# London_EPS-v_2_0.net
KiCad netlist of a schematic drawn in EAGLE
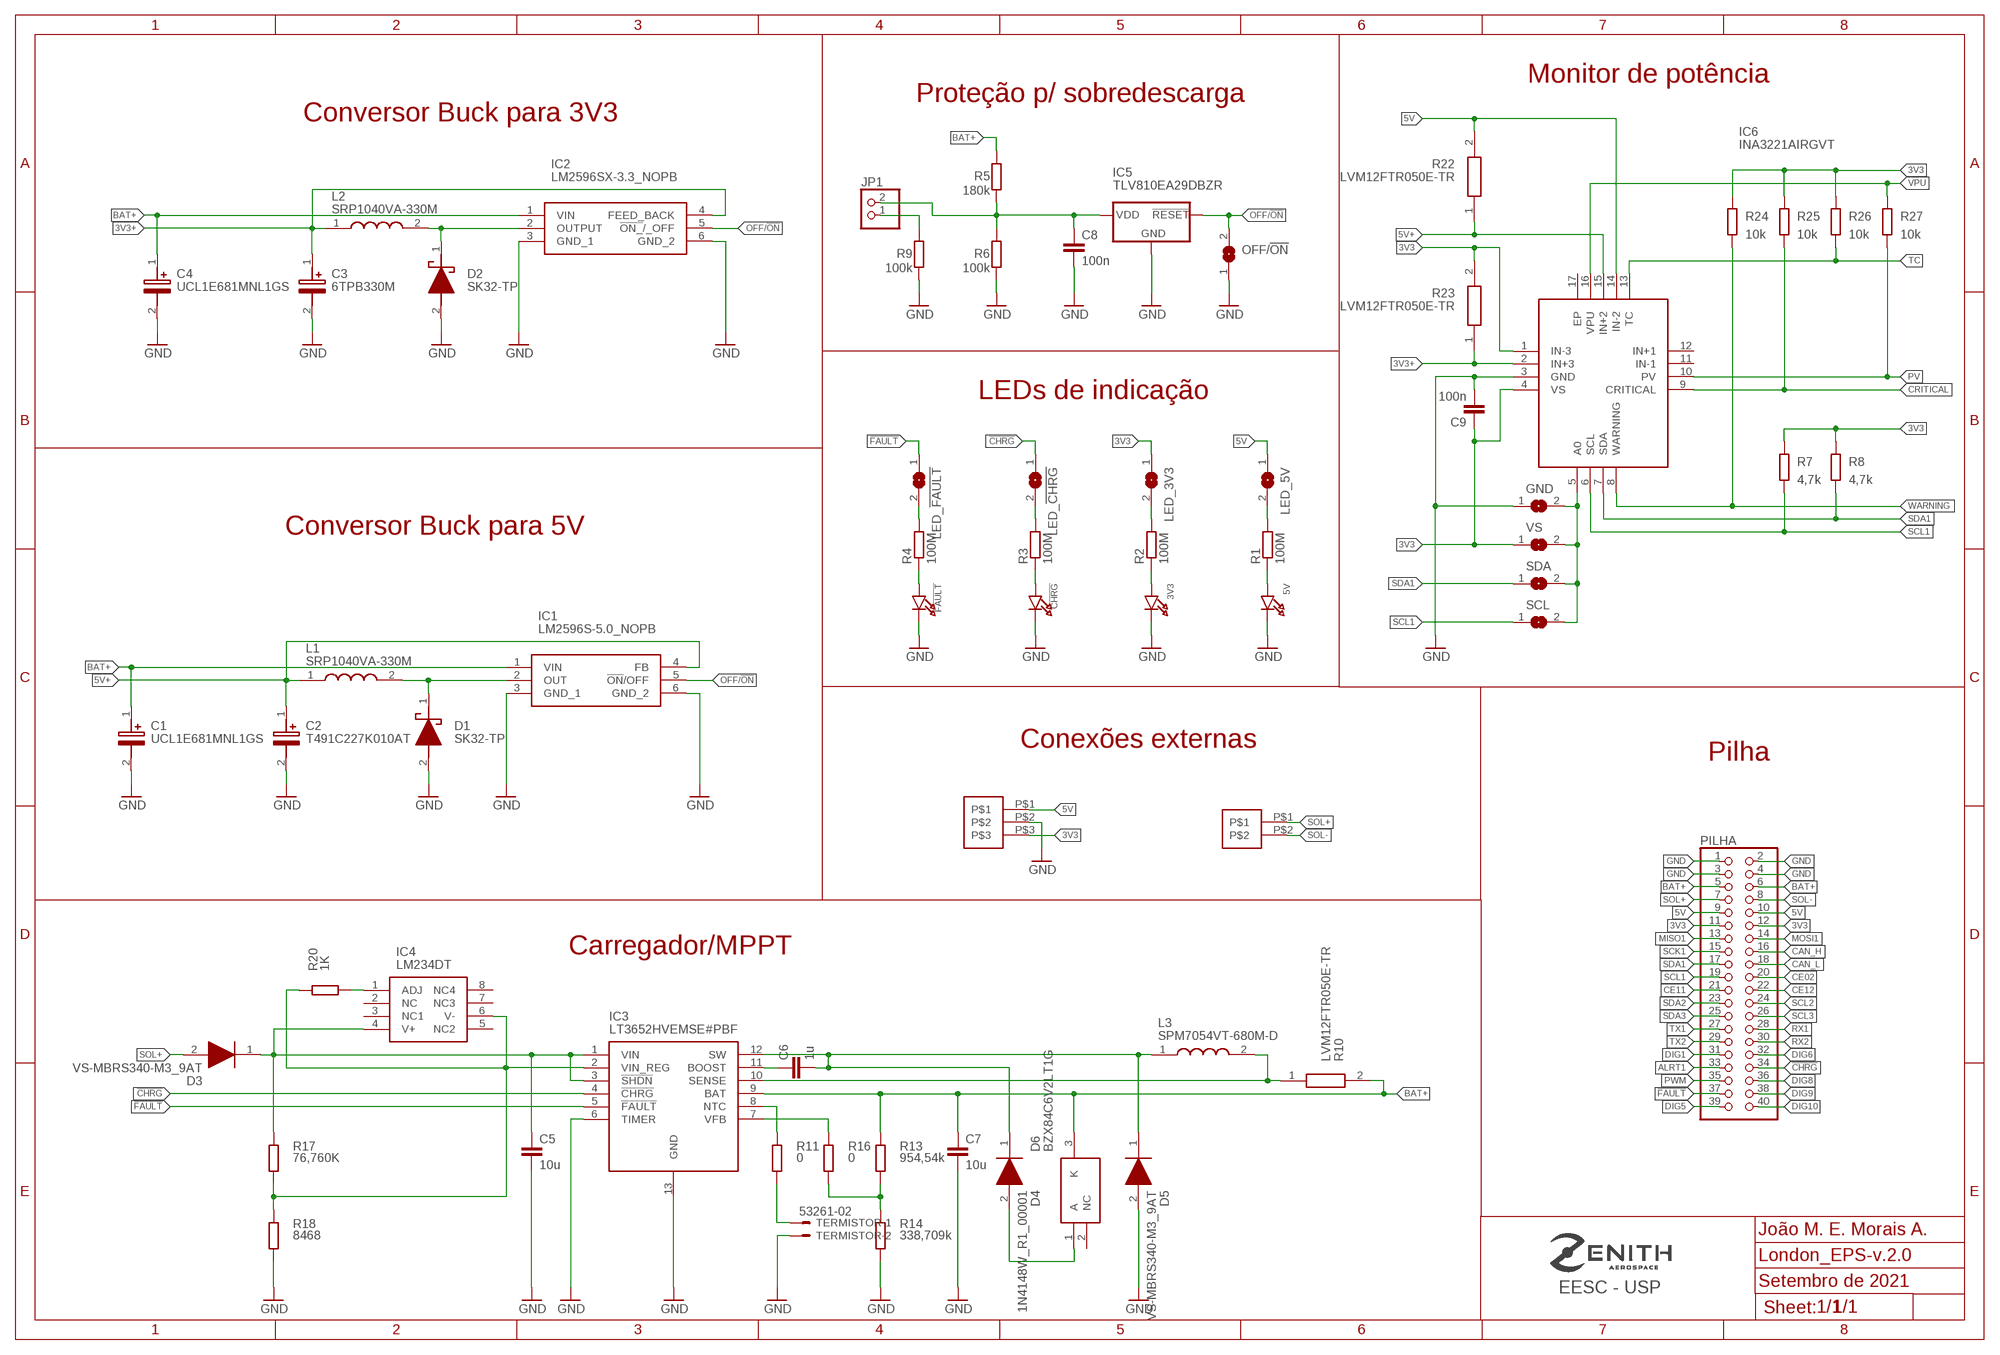
[diagram p0: schematic, sheet 1]

(export (version "E")
  (design (tool "Eeschema 10.0.6"))
  (components
    (comp (ref "!CHRG")
      (value "LED1206")
      (footprint "eagle-import:CHIPLED_1206")
      (libsource (lib "eagle-import") (part "LED1206"))
    )
    (comp (ref "!FAULT")
      (value "LED1206")
      (footprint "eagle-import:CHIPLED_1206")
      (libsource (lib "eagle-import") (part "LED1206"))
    )
    (comp (ref "3V3")
      (value "LED1206")
      (footprint "eagle-import:CHIPLED_1206")
      (libsource (lib "eagle-import") (part "LED1206"))
    )
    (comp (ref "5V")
      (value "LED1206")
      (footprint "eagle-import:CHIPLED_1206")
      (libsource (lib "eagle-import") (part "LED1206"))
    )
    (comp (ref "C1")
      (value "UCL1E681MNL1GS")
      (footprint "eagle-import:CAPAE1030X1400N")
      (fields (field (name "MOUSER_PART_NUMBER") "647-UCL1E681MNL1GS"))
      (libsource (lib "eagle-import") (part "UCL1E681MNL1GS"))
    )
    (comp (ref "C2")
      (value "T491C227K010AT")
      (footprint "eagle-import:CAPPM6032X280N")
      (fields (field (name "MOUSER_PART_NUMBER") "80-T491C227K010AT"))
      (libsource (lib "eagle-import") (part "T491C227K010AT"))
    )
    (comp (ref "C3")
      (value "6TPB330M")
      (footprint "eagle-import:10TPF150ML")
      (fields (field (name "MOUSER_PART_NUMBER") "667-6TPB330M"))
      (libsource (lib "eagle-import") (part "6TPB330M"))
    )
    (comp (ref "C4")
      (value "UCL1E681MNL1GS")
      (footprint "eagle-import:CAPAE1030X1400N")
      (fields (field (name "MOUSER_PART_NUMBER") "647-UCL1E681MNL1GS"))
      (libsource (lib "eagle-import") (part "UCL1E681MNL1GS"))
    )
    (comp (ref "C5")
      (value "10u")
      (footprint "eagle-import:C0805")
      (libsource (lib "eagle-import") (part "C-EUC0805"))
    )
    (comp (ref "C6")
      (value "1u")
      (footprint "eagle-import:C0805")
      (libsource (lib "eagle-import") (part "C-EUC0805"))
    )
    (comp (ref "C7")
      (value "10u")
      (footprint "eagle-import:C0805")
      (libsource (lib "eagle-import") (part "C-EUC0805"))
    )
    (comp (ref "C8")
      (value "100n")
      (footprint "eagle-import:C0805")
      (libsource (lib "eagle-import") (part "C-EUC0805"))
    )
    (comp (ref "C9")
      (value "100n")
      (footprint "eagle-import:C0805")
      (libsource (lib "eagle-import") (part "C-EUC0805"))
    )
    (comp (ref "D1")
      (value "SK32-TP")
      (footprint "eagle-import:DIOM7959X262N@1")
      (fields (field (name "MOUSER_PART_NUMBER") "833-SK32-TP"))
      (libsource (lib "eagle-import") (part "SK32-TP"))
    )
    (comp (ref "D2")
      (value "SK32-TP")
      (footprint "eagle-import:DIOM7959X262N@1")
      (fields (field (name "MOUSER_PART_NUMBER") "833-SK32-TP"))
      (libsource (lib "eagle-import") (part "SK32-TP"))
    )
    (comp (ref "D3")
      (value "VS-MBRS340-M3_9AT")
      (footprint "eagle-import:DIOM7959X262N")
      (fields
        (field (name "MANUFACTURER_PART_NUMBER") "VS-MBRS340-M3/9AT")
        (field (name "MOUSER_PART_NUMBER") "78-VS-MBRS340-M39AT")
      )
      (libsource (lib "eagle-import") (part "VS-MBRS340-M3_9AT"))
    )
    (comp (ref "D4")
      (value "1N4148W_R1_00001")
      (footprint "eagle-import:SOD3816X135N")
      (fields (field (name "MOUSER_PART_NUMBER") "241-1N4148W_R1_00001"))
      (libsource (lib "eagle-import") (part "1N4148W_R1_00001"))
    )
    (comp (ref "D5")
      (value "VS-MBRS340-M3_9AT")
      (footprint "eagle-import:DIOM7959X262N")
      (fields
        (field (name "MANUFACTURER_PART_NUMBER") "VS-MBRS340-M3/9AT")
        (field (name "MOUSER_PART_NUMBER") "78-VS-MBRS340-M39AT")
      )
      (libsource (lib "eagle-import") (part "VS-MBRS340-M3_9AT"))
    )
    (comp (ref "D6")
      (value "BZX84C6V2LT1G")
      (footprint "eagle-import:SOT96P237X111-3N")
      (fields (field (name "MOUSER_PART_NUMBER") "863-BZX84C6V2LT1G"))
      (libsource (lib "eagle-import") (part "BZX84C6V2LT1G"))
    )
    (comp (ref "GND")
      (value "SOLDERJUMPERREFLOW_NOPASTE")
      (footprint "eagle-import:SOLDERJUMPER_REFLOW_NOPASTE")
      (libsource (lib "eagle-import") (part "SOLDERJUMPERREFLOW_NOPASTE"))
    )
    (comp (ref "IC1")
      (value "LM2596S-5.0_NOPB")
      (footprint "eagle-import:KTT0005B")
      (fields
        (field (name "MANUFACTURER_PART_NUMBER") "LM2596S-5.0/NOPB")
        (field (name "MOUSER_PART_NUMBER") "926-LM2596S-5.0/NOPB")
      )
      (libsource (lib "eagle-import") (part "LM2596S-5.0_NOPB"))
    )
    (comp (ref "IC2")
      (value "LM2596SX-3.3_NOPB")
      (footprint "eagle-import:KTT0005B")
      (fields
        (field (name "MANUFACTURER_PART_NUMBER") "LM2596SX-3.3/NOPB")
        (field (name "MOUSER_PART_NUMBER") "926-LM2596SX33NOPB")
      )
      (libsource (lib "eagle-import") (part "LM2596SX-3.3_NOPB"))
    )
    (comp (ref "IC3")
      (value "LT3652HVEMSE#PBF")
      (footprint "eagle-import:SOP65P490X110-13N")
      (fields (field (name "MOUSER_PART_NUMBER") "584-LT3652HVEMSE#PBF"))
      (libsource (lib "eagle-import") (part "LT3652HVEMSE#PBF"))
    )
    (comp (ref "IC4")
      (value "LM234DT")
      (footprint "eagle-import:SOIC127P600X175-8N")
      (fields (field (name "MOUSER_PART_NUMBER") "511-LM234D"))
      (libsource (lib "eagle-import") (part "LM234DT"))
    )
    (comp (ref "IC5")
      (value "TLV810EA29DBZR")
      (footprint "eagle-import:SOT23")
      (libsource (lib "eagle-import") (part "TLV810EA29DBZR"))
    )
    (comp (ref "IC6")
      (value "INA3221AIRGVT")
      (footprint "eagle-import:QFN65P400X400X100-17N")
      (fields (field (name "MOUSER_PART_NUMBER") "595-INA3221AIRGVT"))
      (libsource (lib "eagle-import") (part "INA3221AIRGVT"))
    )
    (comp (ref "JP1")
      (value "PINHD-1X2/90")
      (footprint "eagle-import:1X02_90")
      (libsource (lib "eagle-import") (part "PINHD-1X2/90"))
    )
    (comp (ref "L1")
      (value "SRP1040VA-330M")
      (footprint "eagle-import:INDPM110100X400N")
      (fields (field (name "MOUSER_PART_NUMBER") "652-SRP1040VA-330M"))
      (libsource (lib "eagle-import") (part "SRP1040VA-330M"))
    )
    (comp (ref "L2")
      (value "SRP1040VA-330M")
      (footprint "eagle-import:INDPM110100X400N")
      (fields (field (name "MOUSER_PART_NUMBER") "652-SRP1040VA-330M"))
      (libsource (lib "eagle-import") (part "SRP1040VA-330M"))
    )
    (comp (ref "L3")
      (value "SPM7054VT-680M-D")
      (footprint "eagle-import:SPM7054VT")
      (fields (field (name "MOUSER_PART_NUMBER") "810-SPM7054VT-680M-D"))
      (libsource (lib "eagle-import") (part "SPM7054VT-680M-D"))
    )
    (comp (ref "LED_!CHRG")
      (value "SOLDERJUMPERREFLOW_NOPASTE")
      (footprint "eagle-import:SOLDERJUMPER_REFLOW_NOPASTE")
      (libsource (lib "eagle-import") (part "SOLDERJUMPERREFLOW_NOPASTE"))
    )
    (comp (ref "LED_!FAULT")
      (value "SOLDERJUMPERREFLOW_NOPASTE")
      (footprint "eagle-import:SOLDERJUMPER_REFLOW_NOPASTE")
      (libsource (lib "eagle-import") (part "SOLDERJUMPERREFLOW_NOPASTE"))
    )
    (comp (ref "LED_3V3")
      (value "SOLDERJUMPERREFLOW_NOPASTE")
      (footprint "eagle-import:SOLDERJUMPER_REFLOW_NOPASTE")
      (libsource (lib "eagle-import") (part "SOLDERJUMPERREFLOW_NOPASTE"))
    )
    (comp (ref "LED_5V")
      (value "SOLDERJUMPERREFLOW_NOPASTE")
      (footprint "eagle-import:SOLDERJUMPER_REFLOW_NOPASTE")
      (libsource (lib "eagle-import") (part "SOLDERJUMPERREFLOW_NOPASTE"))
    )
    (comp (ref "OFF/!ON")
      (value "SOLDERJUMPERREFLOW_NOPASTE")
      (footprint "eagle-import:SOLDERJUMPER_REFLOW_NOPASTE")
      (libsource (lib "eagle-import") (part "SOLDERJUMPERREFLOW_NOPASTE"))
    )
    (comp (ref "PILHA")
      (value "PINHD-2X20")
      (footprint "eagle-import:2X20")
      (libsource (lib "eagle-import") (part "PINHD-2X20"))
    )
    (comp (ref "R1")
      (value "100M")
      (footprint "eagle-import:R0805")
      (libsource (lib "eagle-import") (part "R-EU_R0805"))
    )
    (comp (ref "R2")
      (value "100M")
      (footprint "eagle-import:R0805")
      (libsource (lib "eagle-import") (part "R-EU_R0805"))
    )
    (comp (ref "R3")
      (value "100M")
      (footprint "eagle-import:R0805")
      (libsource (lib "eagle-import") (part "R-EU_R0805"))
    )
    (comp (ref "R4")
      (value "100M")
      (footprint "eagle-import:R0805")
      (libsource (lib "eagle-import") (part "R-EU_R0805"))
    )
    (comp (ref "R5")
      (value "180k")
      (footprint "eagle-import:R0805")
      (libsource (lib "eagle-import") (part "R-EU_R0805"))
    )
    (comp (ref "R6")
      (value "100k")
      (footprint "eagle-import:R0805")
      (libsource (lib "eagle-import") (part "R-EU_R0805"))
    )
    (comp (ref "R7")
      (value "4,7k")
      (footprint "eagle-import:R0805")
      (libsource (lib "eagle-import") (part "R-EU_R0805"))
    )
    (comp (ref "R8")
      (value "4,7k")
      (footprint "eagle-import:R0805")
      (libsource (lib "eagle-import") (part "R-EU_R0805"))
    )
    (comp (ref "R9")
      (value "100k")
      (footprint "eagle-import:R0805")
      (libsource (lib "eagle-import") (part "R-EU_R0805"))
    )
    (comp (ref "R10")
      (value "LVM12FTR050E-TR")
      (footprint "eagle-import:RESC3016X70N")
      (fields (field (name "MOUSER_PART_NUMBER") "588-LVM12FTR050E-TR"))
      (libsource (lib "eagle-import") (part "LVM12FTR050E-TR"))
    )
    (comp (ref "R11")
      (value "0")
      (footprint "eagle-import:R0805")
      (libsource (lib "eagle-import") (part "R-EU_R0805"))
    )
    (comp (ref "R13")
      (value "954,54k")
      (footprint "eagle-import:R0805")
      (libsource (lib "eagle-import") (part "R-EU_R0805"))
    )
    (comp (ref "R14")
      (value "338,709k")
      (footprint "eagle-import:R0805")
      (libsource (lib "eagle-import") (part "R-EU_R0805"))
    )
    (comp (ref "R16")
      (value "0")
      (footprint "eagle-import:R0805")
      (libsource (lib "eagle-import") (part "R-EU_R0805"))
    )
    (comp (ref "R17")
      (value "76,760K")
      (footprint "eagle-import:R0805")
      (libsource (lib "eagle-import") (part "R-EU_R0805"))
    )
    (comp (ref "R18")
      (value "8468")
      (footprint "eagle-import:R0805")
      (libsource (lib "eagle-import") (part "R-EU_R0805"))
    )
    (comp (ref "R20")
      (value "1K")
      (footprint "eagle-import:R0805")
      (libsource (lib "eagle-import") (part "R-EU_R0805"))
    )
    (comp (ref "R22")
      (value "LVM12FTR050E-TR")
      (footprint "eagle-import:RESC3016X70N")
      (fields (field (name "MOUSER_PART_NUMBER") "588-LVM12FTR050E-TR"))
      (libsource (lib "eagle-import") (part "LVM12FTR050E-TR"))
    )
    (comp (ref "R23")
      (value "LVM12FTR050E-TR")
      (footprint "eagle-import:RESC3016X70N")
      (fields (field (name "MOUSER_PART_NUMBER") "588-LVM12FTR050E-TR"))
      (libsource (lib "eagle-import") (part "LVM12FTR050E-TR"))
    )
    (comp (ref "R24")
      (value "10k")
      (footprint "eagle-import:R0805")
      (libsource (lib "eagle-import") (part "R-EU_R0805"))
    )
    (comp (ref "R25")
      (value "10k")
      (footprint "eagle-import:R0805")
      (libsource (lib "eagle-import") (part "R-EU_R0805"))
    )
    (comp (ref "R26")
      (value "10k")
      (footprint "eagle-import:R0805")
      (libsource (lib "eagle-import") (part "R-EU_R0805"))
    )
    (comp (ref "R27")
      (value "10k")
      (footprint "eagle-import:R0805")
      (libsource (lib "eagle-import") (part "R-EU_R0805"))
    )
    (comp (ref "SCL")
      (value "SOLDERJUMPERREFLOW_NOPASTE")
      (footprint "eagle-import:SOLDERJUMPER_REFLOW_NOPASTE")
      (libsource (lib "eagle-import") (part "SOLDERJUMPERREFLOW_NOPASTE"))
    )
    (comp (ref "SDA")
      (value "SOLDERJUMPERREFLOW_NOPASTE")
      (footprint "eagle-import:SOLDERJUMPER_REFLOW_NOPASTE")
      (libsource (lib "eagle-import") (part "SOLDERJUMPERREFLOW_NOPASTE"))
    )
    (comp (ref "TERMISTOR")
      (value "53261-02")
      (footprint "eagle-import:53261-02")
      (fields (field (name "MF") "MOLEX"))
      (libsource (lib "eagle-import") (part "53?-02261"))
    )
    (comp (ref "U$1")
      (value "S02B-XASS-1")
      (footprint "eagle-import:S02B-XASS-1")
      (libsource (lib "eagle-import") (part "S02B-XASS-1"))
    )
    (comp (ref "U$2")
      (value "S03B-XASS-1")
      (footprint "eagle-import:S03B-XASS-1")
      (libsource (lib "eagle-import") (part "S03B-XASS-1"))
    )
    (comp (ref "VS")
      (value "SOLDERJUMPERREFLOW_NOPASTE")
      (footprint "eagle-import:SOLDERJUMPER_REFLOW_NOPASTE")
      (libsource (lib "eagle-import") (part "SOLDERJUMPERREFLOW_NOPASTE"))
    )
  )
  (nets
    (net (code "1") (name "/OFF{slash}~{ON}") (class "Default")
      (node (ref "IC1") (pin "5") (pinfunction "~{ON}/OFF_5") (pintype "bidirectional"))
      (node (ref "IC2") (pin "5") (pinfunction "~{ON_}/_OFF_5") (pintype "bidirectional"))
      (node (ref "IC5") (pin "1") (pinfunction "~{RESET}_1") (pintype "passive"))
      (node (ref "OFF/!ON") (pin "2") (pinfunction "2_2") (pintype "passive"))
    )
    (net (code "2") (name "/~{CHRG}") (class "Default")
      (node (ref "IC3") (pin "4") (pinfunction "~{CHRG}_4") (pintype "bidirectional"))
      (node (ref "LED_!CHRG") (pin "1") (pinfunction "1_1") (pintype "passive"))
      (node (ref "PILHA") (pin "34") (pinfunction "34_34") (pintype "passive"))
    )
    (net (code "3") (name "/~{FAULT}") (class "Default")
      (node (ref "IC3") (pin "5") (pinfunction "~{FAULT}_5") (pintype "bidirectional"))
      (node (ref "LED_!FAULT") (pin "1") (pinfunction "1_1") (pintype "passive"))
      (node (ref "PILHA") (pin "37") (pinfunction "37_37") (pintype "passive"))
    )
    (net (code "4") (name "3V3") (class "Default")
      (node (ref "C9") (pin "1") (pinfunction "1_1") (pintype "passive"))
      (node (ref "IC6") (pin "1") (pinfunction "IN-3_1") (pintype "bidirectional"))
      (node (ref "IC6") (pin "4") (pinfunction "VS_4") (pintype "bidirectional"))
      (node (ref "LED_3V3") (pin "1") (pinfunction "1_1") (pintype "passive"))
      (node (ref "PILHA") (pin "11") (pinfunction "11_11") (pintype "passive"))
      (node (ref "PILHA") (pin "12") (pinfunction "12_12") (pintype "passive"))
      (node (ref "R23") (pin "2") (pinfunction "2_2") (pintype "bidirectional"))
      (node (ref "R24") (pin "2") (pinfunction "2_2") (pintype "passive"))
      (node (ref "R25") (pin "2") (pinfunction "2_2") (pintype "passive"))
      (node (ref "R26") (pin "2") (pinfunction "2_2") (pintype "passive"))
      (node (ref "R7") (pin "2") (pinfunction "2_2") (pintype "passive"))
      (node (ref "R8") (pin "2") (pinfunction "2_2") (pintype "passive"))
      (node (ref "U$2") (pin "P$3") (pinfunction "P$3_P$3") (pintype "bidirectional"))
      (node (ref "VS") (pin "1") (pinfunction "1_1") (pintype "passive"))
    )
    (net (code "5") (name "3V3+") (class "Default")
      (node (ref "C3") (pin "1") (pinfunction "+_1") (pintype "bidirectional"))
      (node (ref "IC2") (pin "4") (pinfunction "FEED_BACK_4") (pintype "bidirectional"))
      (node (ref "IC6") (pin "2") (pinfunction "IN+3_2") (pintype "bidirectional"))
      (node (ref "L2") (pin "1") (pinfunction "1_1") (pintype "bidirectional"))
      (node (ref "R23") (pin "1") (pinfunction "1_1") (pintype "bidirectional"))
    )
    (net (code "6") (name "5V") (class "Default")
      (node (ref "IC6") (pin "14") (pinfunction "IN-2_14") (pintype "bidirectional"))
      (node (ref "LED_5V") (pin "1") (pinfunction "1_1") (pintype "passive"))
      (node (ref "PILHA") (pin "10") (pinfunction "10_10") (pintype "passive"))
      (node (ref "PILHA") (pin "9") (pinfunction "9_9") (pintype "passive"))
      (node (ref "R22") (pin "2") (pinfunction "2_2") (pintype "bidirectional"))
      (node (ref "U$2") (pin "P$1") (pinfunction "P$1_P$1") (pintype "bidirectional"))
    )
    (net (code "7") (name "5V+") (class "Default")
      (node (ref "C2") (pin "1") (pinfunction "+_1") (pintype "bidirectional"))
      (node (ref "IC1") (pin "4") (pinfunction "FB_4") (pintype "bidirectional"))
      (node (ref "IC6") (pin "15") (pinfunction "IN+2_15") (pintype "bidirectional"))
      (node (ref "L1") (pin "1") (pinfunction "1_1") (pintype "bidirectional"))
      (node (ref "R22") (pin "1") (pinfunction "1_1") (pintype "bidirectional"))
    )
    (net (code "8") (name "ALRT1") (class "Default")
      (node (ref "PILHA") (pin "33") (pinfunction "33_33") (pintype "passive"))
    )
    (net (code "9") (name "BAT+") (class "Default")
      (node (ref "C1") (pin "1") (pinfunction "+_1") (pintype "bidirectional"))
      (node (ref "C4") (pin "1") (pinfunction "+_1") (pintype "bidirectional"))
      (node (ref "C7") (pin "1") (pinfunction "1_1") (pintype "passive"))
      (node (ref "D6") (pin "3") (pinfunction "K_3") (pintype "bidirectional"))
      (node (ref "IC1") (pin "1") (pinfunction "VIN_1") (pintype "bidirectional"))
      (node (ref "IC2") (pin "1") (pinfunction "VIN_1") (pintype "bidirectional"))
      (node (ref "IC3") (pin "9") (pinfunction "BAT_9") (pintype "bidirectional"))
      (node (ref "PILHA") (pin "5") (pinfunction "5_5") (pintype "passive"))
      (node (ref "PILHA") (pin "6") (pinfunction "6_6") (pintype "passive"))
      (node (ref "R10") (pin "2") (pinfunction "2_2") (pintype "bidirectional"))
      (node (ref "R13") (pin "1") (pinfunction "1_1") (pintype "passive"))
      (node (ref "R5") (pin "1") (pinfunction "1_1") (pintype "passive"))
    )
    (net (code "10") (name "CAN_H") (class "Default")
      (node (ref "PILHA") (pin "16") (pinfunction "16_16") (pintype "passive"))
    )
    (net (code "11") (name "CAN_L") (class "Default")
      (node (ref "PILHA") (pin "18") (pinfunction "18_18") (pintype "passive"))
    )
    (net (code "12") (name "CE02") (class "Default")
      (node (ref "PILHA") (pin "20") (pinfunction "20_20") (pintype "passive"))
    )
    (net (code "13") (name "CE11") (class "Default")
      (node (ref "PILHA") (pin "21") (pinfunction "21_21") (pintype "passive"))
    )
    (net (code "14") (name "CE12") (class "Default")
      (node (ref "PILHA") (pin "22") (pinfunction "22_22") (pintype "passive"))
    )
    (net (code "15") (name "CRITICAL") (class "Default")
      (node (ref "IC6") (pin "9") (pinfunction "CRITICAL_9") (pintype "bidirectional"))
      (node (ref "R25") (pin "1") (pinfunction "1_1") (pintype "passive"))
    )
    (net (code "16") (name "DIG1") (class "Default")
      (node (ref "PILHA") (pin "31") (pinfunction "31_31") (pintype "passive"))
    )
    (net (code "17") (name "DIG5") (class "Default")
      (node (ref "PILHA") (pin "39") (pinfunction "39_39") (pintype "passive"))
    )
    (net (code "18") (name "DIG6") (class "Default")
      (node (ref "PILHA") (pin "32") (pinfunction "32_32") (pintype "passive"))
    )
    (net (code "19") (name "DIG8") (class "Default")
      (node (ref "PILHA") (pin "36") (pinfunction "36_36") (pintype "passive"))
    )
    (net (code "20") (name "DIG9") (class "Default")
      (node (ref "PILHA") (pin "38") (pinfunction "38_38") (pintype "passive"))
    )
    (net (code "21") (name "DIG10") (class "Default")
      (node (ref "PILHA") (pin "40") (pinfunction "40_40") (pintype "passive"))
    )
    (net (code "22") (name "GND") (class "Default")
      (node (ref "!CHRG") (pin "C") (pinfunction "C_C") (pintype "passive"))
      (node (ref "!FAULT") (pin "C") (pinfunction "C_C") (pintype "passive"))
      (node (ref "3V3") (pin "C") (pinfunction "C_C") (pintype "passive"))
      (node (ref "5V") (pin "C") (pinfunction "C_C") (pintype "passive"))
      (node (ref "C1") (pin "2") (pinfunction "-_2") (pintype "bidirectional"))
      (node (ref "C2") (pin "2") (pinfunction "-_2") (pintype "bidirectional"))
      (node (ref "C3") (pin "2") (pinfunction "-_2") (pintype "bidirectional"))
      (node (ref "C4") (pin "2") (pinfunction "-_2") (pintype "bidirectional"))
      (node (ref "C5") (pin "2") (pinfunction "2_2") (pintype "passive"))
      (node (ref "C7") (pin "2") (pinfunction "2_2") (pintype "passive"))
      (node (ref "C8") (pin "2") (pinfunction "2_2") (pintype "passive"))
      (node (ref "C9") (pin "2") (pinfunction "2_2") (pintype "passive"))
      (node (ref "D1") (pin "2") (pinfunction "A_2") (pintype "bidirectional"))
      (node (ref "D2") (pin "2") (pinfunction "A_2") (pintype "bidirectional"))
      (node (ref "D5") (pin "2") (pinfunction "A_2") (pintype "bidirectional"))
      (node (ref "GND") (pin "1") (pinfunction "1_1") (pintype "passive"))
      (node (ref "IC1") (pin "3") (pinfunction "GND_1_3") (pintype "bidirectional"))
      (node (ref "IC1") (pin "6") (pinfunction "GND_2_6") (pintype "bidirectional"))
      (node (ref "IC2") (pin "3") (pinfunction "GND_1_3") (pintype "bidirectional"))
      (node (ref "IC2") (pin "6") (pinfunction "GND_2_6") (pintype "bidirectional"))
      (node (ref "IC3") (pin "13") (pinfunction "GND_13") (pintype "bidirectional"))
      (node (ref "IC3") (pin "6") (pinfunction "TIMER_6") (pintype "bidirectional"))
      (node (ref "IC5") (pin "2") (pinfunction "GND_2") (pintype "input"))
      (node (ref "IC6") (pin "3") (pinfunction "GND_3") (pintype "bidirectional"))
      (node (ref "OFF/!ON") (pin "1") (pinfunction "1_1") (pintype "passive"))
      (node (ref "PILHA") (pin "1") (pinfunction "1_1") (pintype "passive"))
      (node (ref "PILHA") (pin "2") (pinfunction "2_2") (pintype "passive"))
      (node (ref "PILHA") (pin "3") (pinfunction "3_3") (pintype "passive"))
      (node (ref "PILHA") (pin "4") (pinfunction "4_4") (pintype "passive"))
      (node (ref "R14") (pin "2") (pinfunction "2_2") (pintype "passive"))
      (node (ref "R18") (pin "2") (pinfunction "2_2") (pintype "passive"))
      (node (ref "R6") (pin "2") (pinfunction "2_2") (pintype "passive"))
      (node (ref "R9") (pin "2") (pinfunction "2_2") (pintype "passive"))
      (node (ref "TERMISTOR") (pin "2") (pinfunction "S_2") (pintype "passive"))
      (node (ref "U$2") (pin "P$2") (pinfunction "P$2_P$2") (pintype "bidirectional"))
    )
    (net (code "23") (name "MISO1") (class "Default")
      (node (ref "PILHA") (pin "13") (pinfunction "13_13") (pintype "passive"))
    )
    (net (code "24") (name "MOSI1") (class "Default")
      (node (ref "PILHA") (pin "14") (pinfunction "14_14") (pintype "passive"))
    )
    (net (code "25") (name "Net-(!CHRG-PadA)") (class "Default")
      (node (ref "!CHRG") (pin "A") (pinfunction "A_A") (pintype "passive"))
      (node (ref "R3") (pin "1") (pinfunction "1_1") (pintype "passive"))
    )
    (net (code "26") (name "Net-(!FAULT-PadA)") (class "Default")
      (node (ref "!FAULT") (pin "A") (pinfunction "A_A") (pintype "passive"))
      (node (ref "R4") (pin "1") (pinfunction "1_1") (pintype "passive"))
    )
    (net (code "27") (name "Net-(3V3-PadA)") (class "Default")
      (node (ref "3V3") (pin "A") (pinfunction "A_A") (pintype "passive"))
      (node (ref "R2") (pin "1") (pinfunction "1_1") (pintype "passive"))
    )
    (net (code "28") (name "Net-(5V-PadA)") (class "Default")
      (node (ref "5V") (pin "A") (pinfunction "A_A") (pintype "passive"))
      (node (ref "R1") (pin "1") (pinfunction "1_1") (pintype "passive"))
    )
    (net (code "29") (name "Net-(D1-K)") (class "Default")
      (node (ref "D1") (pin "1") (pinfunction "K_1") (pintype "bidirectional"))
      (node (ref "IC1") (pin "2") (pinfunction "OUT_2") (pintype "bidirectional"))
      (node (ref "L1") (pin "2") (pinfunction "2_2") (pintype "bidirectional"))
    )
    (net (code "30") (name "Net-(D2-K)") (class "Default")
      (node (ref "D2") (pin "1") (pinfunction "K_1") (pintype "bidirectional"))
      (node (ref "IC2") (pin "2") (pinfunction "OUTPUT_2") (pintype "bidirectional"))
      (node (ref "L2") (pin "2") (pinfunction "2_2") (pintype "bidirectional"))
    )
    (net (code "31") (name "Net-(D3-K)") (class "Default")
      (node (ref "C5") (pin "1") (pinfunction "1_1") (pintype "passive"))
      (node (ref "D3") (pin "1") (pinfunction "K_1") (pintype "bidirectional"))
      (node (ref "IC3") (pin "1") (pinfunction "VIN_1") (pintype "bidirectional"))
      (node (ref "IC3") (pin "3") (pinfunction "~{SHDN}_3") (pintype "bidirectional"))
      (node (ref "IC4") (pin "4") (pinfunction "V+_4") (pintype "bidirectional"))
      (node (ref "R17") (pin "1") (pinfunction "1_1") (pintype "passive"))
    )
    (net (code "32") (name "Net-(D4-A)") (class "Default")
      (node (ref "D4") (pin "2") (pinfunction "A_2") (pintype "bidirectional"))
      (node (ref "D6") (pin "1") (pinfunction "A_1") (pintype "bidirectional"))
    )
    (net (code "33") (name "Net-(D4-K)") (class "Default")
      (node (ref "C6") (pin "2") (pinfunction "2_2") (pintype "passive"))
      (node (ref "D4") (pin "1") (pinfunction "K_1") (pintype "bidirectional"))
      (node (ref "D5") (pin "1") (pinfunction "K_1") (pintype "bidirectional"))
      (node (ref "IC3") (pin "12") (pinfunction "SW_12") (pintype "bidirectional"))
      (node (ref "L3") (pin "1") (pinfunction "1_1") (pintype "bidirectional"))
    )
    (net (code "34") (name "Net-(IC3-BOOST)") (class "Default")
      (node (ref "C6") (pin "1") (pinfunction "1_1") (pintype "passive"))
      (node (ref "IC3") (pin "11") (pinfunction "BOOST_11") (pintype "bidirectional"))
    )
    (net (code "35") (name "Net-(IC3-NTC)") (class "Default")
      (node (ref "IC3") (pin "8") (pinfunction "NTC_8") (pintype "bidirectional"))
      (node (ref "R11") (pin "1") (pinfunction "1_1") (pintype "passive"))
    )
    (net (code "36") (name "Net-(IC3-SENSE)") (class "Default")
      (node (ref "IC3") (pin "10") (pinfunction "SENSE_10") (pintype "bidirectional"))
      (node (ref "L3") (pin "2") (pinfunction "2_2") (pintype "bidirectional"))
      (node (ref "R10") (pin "1") (pinfunction "1_1") (pintype "bidirectional"))
    )
    (net (code "37") (name "Net-(IC3-VFB)") (class "Default")
      (node (ref "IC3") (pin "7") (pinfunction "VFB_7") (pintype "bidirectional"))
      (node (ref "R16") (pin "1") (pinfunction "1_1") (pintype "passive"))
    )
    (net (code "38") (name "Net-(IC3-VIN_REG)") (class "Default")
      (node (ref "IC3") (pin "2") (pinfunction "VIN_REG_2") (pintype "bidirectional"))
      (node (ref "IC4") (pin "6") (pinfunction "V-_6") (pintype "bidirectional"))
      (node (ref "R17") (pin "2") (pinfunction "2_2") (pintype "passive"))
      (node (ref "R18") (pin "1") (pinfunction "1_1") (pintype "passive"))
      (node (ref "R20") (pin "1") (pinfunction "1_1") (pintype "passive"))
    )
    (net (code "39") (name "Net-(IC4-ADJ)") (class "Default")
      (node (ref "IC4") (pin "1") (pinfunction "ADJ_1") (pintype "bidirectional"))
      (node (ref "R20") (pin "2") (pinfunction "2_2") (pintype "passive"))
    )
    (net (code "40") (name "Net-(IC5-VDD)") (class "Default")
      (node (ref "C8") (pin "1") (pinfunction "1_1") (pintype "passive"))
      (node (ref "IC5") (pin "3") (pinfunction "VDD_3") (pintype "input"))
      (node (ref "JP1") (pin "2") (pinfunction "2_2") (pintype "passive"))
      (node (ref "R5") (pin "2") (pinfunction "2_2") (pintype "passive"))
      (node (ref "R6") (pin "1") (pinfunction "1_1") (pintype "passive"))
    )
    (net (code "41") (name "Net-(IC6-A0)") (class "Default")
      (node (ref "GND") (pin "2") (pinfunction "2_2") (pintype "passive"))
      (node (ref "IC6") (pin "5") (pinfunction "A0_5") (pintype "bidirectional"))
      (node (ref "SCL") (pin "2") (pinfunction "2_2") (pintype "passive"))
      (node (ref "SDA") (pin "2") (pinfunction "2_2") (pintype "passive"))
      (node (ref "VS") (pin "2") (pinfunction "2_2") (pintype "passive"))
    )
    (net (code "42") (name "Net-(JP1-Pad1)") (class "Default")
      (node (ref "JP1") (pin "1") (pinfunction "1_1") (pintype "passive"))
      (node (ref "R9") (pin "1") (pinfunction "1_1") (pintype "passive"))
    )
    (net (code "43") (name "Net-(LED_!CHRG-Pad2)") (class "Default")
      (node (ref "LED_!CHRG") (pin "2") (pinfunction "2_2") (pintype "passive"))
      (node (ref "R3") (pin "2") (pinfunction "2_2") (pintype "passive"))
    )
    (net (code "44") (name "Net-(LED_!FAULT-Pad2)") (class "Default")
      (node (ref "LED_!FAULT") (pin "2") (pinfunction "2_2") (pintype "passive"))
      (node (ref "R4") (pin "2") (pinfunction "2_2") (pintype "passive"))
    )
    (net (code "45") (name "Net-(LED_3V3-Pad2)") (class "Default")
      (node (ref "LED_3V3") (pin "2") (pinfunction "2_2") (pintype "passive"))
      (node (ref "R2") (pin "2") (pinfunction "2_2") (pintype "passive"))
    )
    (net (code "46") (name "Net-(LED_5V-Pad2)") (class "Default")
      (node (ref "LED_5V") (pin "2") (pinfunction "2_2") (pintype "passive"))
      (node (ref "R1") (pin "2") (pinfunction "2_2") (pintype "passive"))
    )
    (net (code "47") (name "Net-(R13-Pad2)") (class "Default")
      (node (ref "R13") (pin "2") (pinfunction "2_2") (pintype "passive"))
      (node (ref "R14") (pin "1") (pinfunction "1_1") (pintype "passive"))
      (node (ref "R16") (pin "2") (pinfunction "2_2") (pintype "passive"))
    )
    (net (code "48") (name "Net-(TERMISTORA-S)") (class "Default")
      (node (ref "R11") (pin "2") (pinfunction "2_2") (pintype "passive"))
      (node (ref "TERMISTOR") (pin "1") (pinfunction "S_1") (pintype "passive"))
    )
    (net (code "49") (name "PV") (class "Default")
      (node (ref "IC6") (pin "10") (pinfunction "PV_10") (pintype "bidirectional"))
      (node (ref "R27") (pin "1") (pinfunction "1_1") (pintype "passive"))
    )
    (net (code "50") (name "PWM") (class "Default")
      (node (ref "PILHA") (pin "35") (pinfunction "35_35") (pintype "passive"))
    )
    (net (code "51") (name "RX1") (class "Default")
      (node (ref "PILHA") (pin "28") (pinfunction "28_28") (pintype "passive"))
    )
    (net (code "52") (name "RX2") (class "Default")
      (node (ref "PILHA") (pin "30") (pinfunction "30_30") (pintype "passive"))
    )
    (net (code "53") (name "SCK1") (class "Default")
      (node (ref "PILHA") (pin "15") (pinfunction "15_15") (pintype "passive"))
    )
    (net (code "54") (name "SCL1") (class "Default")
      (node (ref "IC6") (pin "6") (pinfunction "SCL_6") (pintype "bidirectional"))
      (node (ref "PILHA") (pin "19") (pinfunction "19_19") (pintype "passive"))
      (node (ref "R7") (pin "1") (pinfunction "1_1") (pintype "passive"))
      (node (ref "SCL") (pin "1") (pinfunction "1_1") (pintype "passive"))
    )
    (net (code "55") (name "SCL2") (class "Default")
      (node (ref "PILHA") (pin "24") (pinfunction "24_24") (pintype "passive"))
    )
    (net (code "56") (name "SCL3") (class "Default")
      (node (ref "PILHA") (pin "26") (pinfunction "26_26") (pintype "passive"))
    )
    (net (code "57") (name "SDA1") (class "Default")
      (node (ref "IC6") (pin "7") (pinfunction "SDA_7") (pintype "bidirectional"))
      (node (ref "PILHA") (pin "17") (pinfunction "17_17") (pintype "passive"))
      (node (ref "R8") (pin "1") (pinfunction "1_1") (pintype "passive"))
      (node (ref "SDA") (pin "1") (pinfunction "1_1") (pintype "passive"))
    )
    (net (code "58") (name "SDA2") (class "Default")
      (node (ref "PILHA") (pin "23") (pinfunction "23_23") (pintype "passive"))
    )
    (net (code "59") (name "SDA3") (class "Default")
      (node (ref "PILHA") (pin "25") (pinfunction "25_25") (pintype "passive"))
    )
    (net (code "60") (name "SOL+") (class "Default")
      (node (ref "D3") (pin "2") (pinfunction "A_2") (pintype "bidirectional"))
      (node (ref "PILHA") (pin "7") (pinfunction "7_7") (pintype "passive"))
      (node (ref "U$1") (pin "P$1") (pinfunction "P$1_P$1") (pintype "bidirectional"))
    )
    (net (code "61") (name "SOL-") (class "Default")
      (node (ref "PILHA") (pin "8") (pinfunction "8_8") (pintype "passive"))
      (node (ref "U$1") (pin "P$2") (pinfunction "P$2_P$2") (pintype "bidirectional"))
    )
    (net (code "62") (name "TC") (class "Default")
      (node (ref "IC6") (pin "13") (pinfunction "TC_13") (pintype "bidirectional"))
      (node (ref "R26") (pin "1") (pinfunction "1_1") (pintype "passive"))
    )
    (net (code "63") (name "TX1") (class "Default")
      (node (ref "PILHA") (pin "27") (pinfunction "27_27") (pintype "passive"))
    )
    (net (code "64") (name "TX2") (class "Default")
      (node (ref "PILHA") (pin "29") (pinfunction "29_29") (pintype "passive"))
    )
    (net (code "65") (name "VPU") (class "Default")
      (node (ref "IC6") (pin "16") (pinfunction "VPU_16") (pintype "bidirectional"))
      (node (ref "R27") (pin "2") (pinfunction "2_2") (pintype "passive"))
    )
    (net (code "66") (name "WARNING") (class "Default")
      (node (ref "IC6") (pin "8") (pinfunction "WARNING_8") (pintype "bidirectional"))
      (node (ref "R24") (pin "1") (pinfunction "1_1") (pintype "passive"))
    )
    (net (code "67") (name "unconnected-(D6-NC-Pad2)") (class "Default")
      (node (ref "D6") (pin "2") (pinfunction "NC_2") (pintype "no_connect"))
    )
    (net (code "68") (name "unconnected-(IC4-NC-Pad2)") (class "Default")
      (node (ref "IC4") (pin "2") (pinfunction "NC_2") (pintype "no_connect"))
    )
    (net (code "69") (name "unconnected-(IC4-NC1-Pad3)") (class "Default")
      (node (ref "IC4") (pin "3") (pinfunction "NC1_3") (pintype "bidirectional"))
    )
    (net (code "70") (name "unconnected-(IC4-NC2-Pad5)") (class "Default")
      (node (ref "IC4") (pin "5") (pinfunction "NC2_5") (pintype "bidirectional"))
    )
    (net (code "71") (name "unconnected-(IC4-NC3-Pad7)") (class "Default")
      (node (ref "IC4") (pin "7") (pinfunction "NC3_7") (pintype "bidirectional"))
    )
    (net (code "72") (name "unconnected-(IC4-NC4-Pad8)") (class "Default")
      (node (ref "IC4") (pin "8") (pinfunction "NC4_8") (pintype "bidirectional"))
    )
    (net (code "73") (name "unconnected-(IC6-EP-Pad17)") (class "Default")
      (node (ref "IC6") (pin "17") (pinfunction "EP_17") (pintype "bidirectional"))
    )
    (net (code "74") (name "unconnected-(IC6-IN+1-Pad12)") (class "Default")
      (node (ref "IC6") (pin "12") (pinfunction "IN+1_12") (pintype "bidirectional"))
    )
    (net (code "75") (name "unconnected-(IC6-IN-1-Pad11)") (class "Default")
      (node (ref "IC6") (pin "11") (pinfunction "IN-1_11") (pintype "bidirectional"))
    )
  )
)
